# DAC.net
KiCad netlist of a schematic drawn in Altium Designer
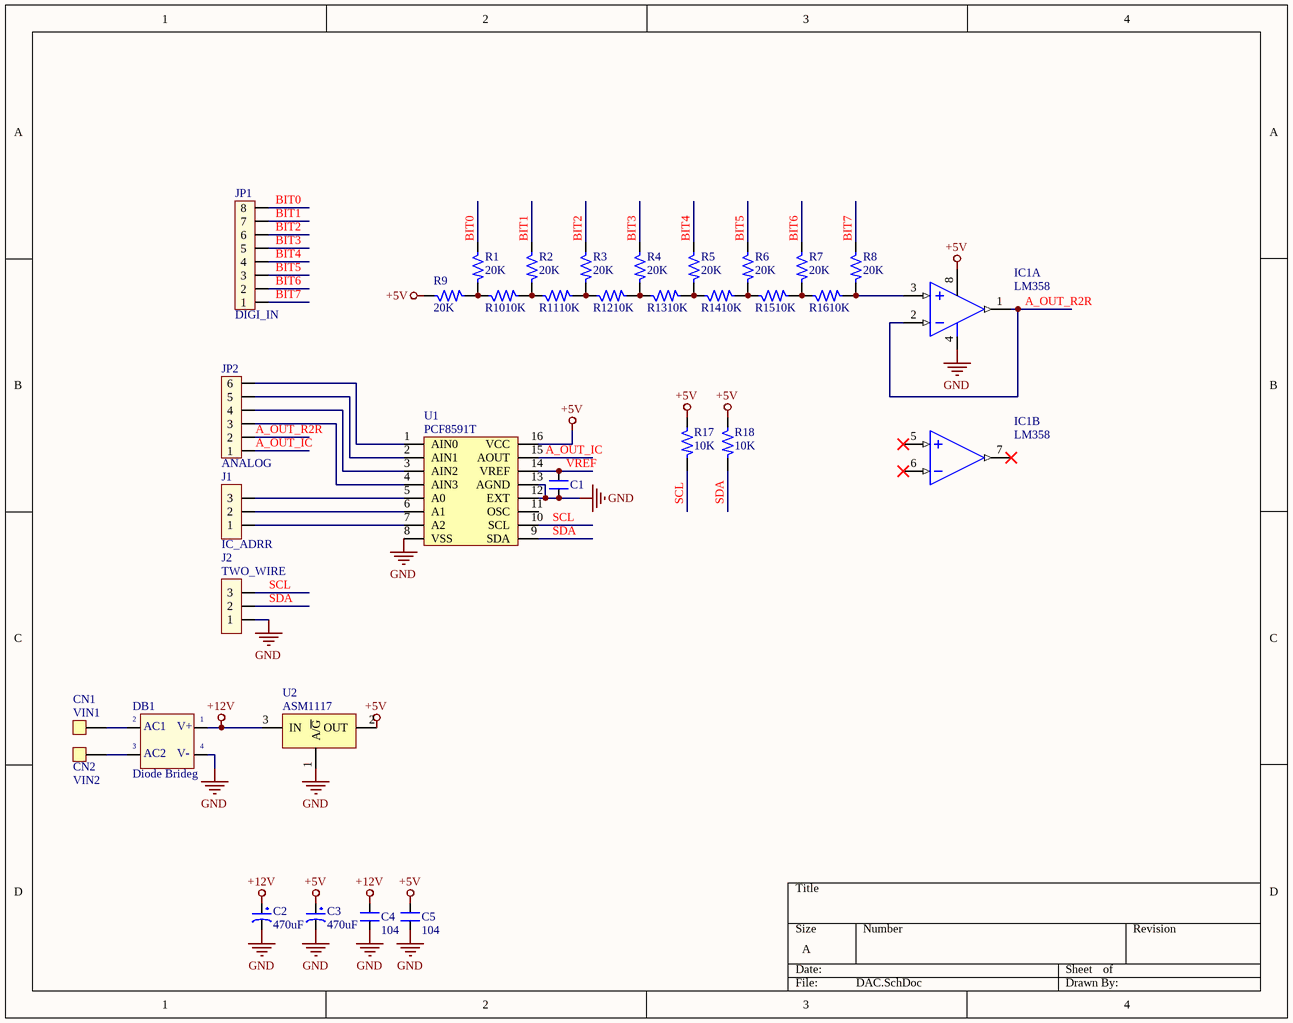
[diagram p0: DAC.SchDoc]

(export (version "E")
  (design (tool "Eeschema 10.0.6"))
  (components
    (comp (ref "C1")
      (value "104")
      (footprint "C-0805")
      (fields (field (name "DESIGNED BY") "VanDungEvn"))
      (libsource (lib "syhaunguyen") (part "CN"))
    )
    (comp (ref "C2")
      (value "470uF")
      (footprint "C-ALU-D6.5")
      (description "Cap P  0,1uF < 22uF , 16 - 50V")
      (libsource (lib "PART") (part "CP1"))
    )
    (comp (ref "C3")
      (value "470uF")
      (footprint "C-ALU-D6.5")
      (description "Cap P  0,1uF < 22uF , 16 - 50V")
      (libsource (lib "PART") (part "CP1"))
    )
    (comp (ref "C4")
      (value "104")
      (footprint "C-0805")
      (fields (field (name "DESIGNED BY") "VanDungEvn"))
      (libsource (lib "syhaunguyen") (part "CN"))
    )
    (comp (ref "C5")
      (value "104")
      (footprint "C-0805")
      (fields (field (name "DESIGNED BY") "VanDungEvn"))
      (libsource (lib "syhaunguyen") (part "CN"))
    )
    (comp (ref "CN1")
      (value "VIN1")
      (footprint "M3")
      (libsource (lib "doAnTotNghiep2017Lib") (part "COCDONGM3"))
    )
    (comp (ref "CN2")
      (value "VIN2")
      (footprint "M3")
      (libsource (lib "doAnTotNghiep2017Lib") (part "COCDONGM3"))
    )
    (comp (ref "DB1")
      (value "Diode Brideg")
      (footprint "D-DB-1A-SMD")
      (description "Convert AC to DC voltage, 4 pin")
      (libsource (lib "PART") (part "DB"))
    )
    (comp (ref "IC1")
      (value "LM358")
      (footprint "SOP-8")
      (description "Low-Power Dual Operational Amplifier")
      (libsource (lib "syhaunguyen") (part "LM358"))
    )
    (comp (ref "J1")
      (value "IC_ADRR")
      (footprint "JP3")
      (description "Jumper 3")
      (libsource (lib "syhaunguyen") (part "JP3"))
    )
    (comp (ref "J2")
      (value "TWO_WIRE")
      (footprint "JP3")
      (description "Jumper 3")
      (libsource (lib "syhaunguyen") (part "JP3"))
    )
    (comp (ref "JP1")
      (value "DIGI_IN")
      (footprint "JP8")
      (description "JP8 PIN")
      (libsource (lib "syhaunguyen") (part "JP8"))
    )
    (comp (ref "JP2")
      (value "ANALOG")
      (footprint "JP6")
      (description "JP6 PIN")
      (libsource (lib "syhaunguyen") (part "JP6"))
    )
    (comp (ref "R1")
      (value "20K")
      (footprint "R-0805")
      (description "Resistor 1/4W")
      (libsource (lib "syhaunguyen") (part "R"))
    )
    (comp (ref "R2")
      (value "20K")
      (footprint "R-0805")
      (description "Resistor 1/4W")
      (libsource (lib "syhaunguyen") (part "R"))
    )
    (comp (ref "R3")
      (value "20K")
      (footprint "R-0805")
      (description "Resistor 1/4W")
      (libsource (lib "syhaunguyen") (part "R"))
    )
    (comp (ref "R4")
      (value "20K")
      (footprint "R-0805")
      (description "Resistor 1/4W")
      (libsource (lib "syhaunguyen") (part "R"))
    )
    (comp (ref "R5")
      (value "20K")
      (footprint "R-0805")
      (description "Resistor 1/4W")
      (libsource (lib "syhaunguyen") (part "R"))
    )
    (comp (ref "R6")
      (value "20K")
      (footprint "R-0805")
      (description "Resistor 1/4W")
      (libsource (lib "syhaunguyen") (part "R"))
    )
    (comp (ref "R7")
      (value "20K")
      (footprint "R-0805")
      (description "Resistor 1/4W")
      (libsource (lib "syhaunguyen") (part "R"))
    )
    (comp (ref "R8")
      (value "20K")
      (footprint "R-0805")
      (description "Resistor 1/4W")
      (libsource (lib "syhaunguyen") (part "R"))
    )
    (comp (ref "R9")
      (value "20K")
      (footprint "R-0805")
      (description "Resistor 1/4W")
      (libsource (lib "syhaunguyen") (part "R"))
    )
    (comp (ref "R10")
      (value "10K")
      (footprint "R-0805")
      (description "Resistor 1/4W")
      (libsource (lib "syhaunguyen") (part "R"))
    )
    (comp (ref "R11")
      (value "10K")
      (footprint "R-0805")
      (description "Resistor 1/4W")
      (libsource (lib "syhaunguyen") (part "R"))
    )
    (comp (ref "R12")
      (value "10K")
      (footprint "R-0805")
      (description "Resistor 1/4W")
      (libsource (lib "syhaunguyen") (part "R"))
    )
    (comp (ref "R13")
      (value "10K")
      (footprint "R-0805")
      (description "Resistor 1/4W")
      (libsource (lib "syhaunguyen") (part "R"))
    )
    (comp (ref "R14")
      (value "10K")
      (footprint "R-0805")
      (description "Resistor 1/4W")
      (libsource (lib "syhaunguyen") (part "R"))
    )
    (comp (ref "R15")
      (value "10K")
      (footprint "R-0805")
      (description "Resistor 1/4W")
      (libsource (lib "syhaunguyen") (part "R"))
    )
    (comp (ref "R16")
      (value "10K")
      (footprint "R-0805")
      (description "Resistor 1/4W")
      (libsource (lib "syhaunguyen") (part "R"))
    )
    (comp (ref "R17")
      (value "10K")
      (footprint "R-0805")
      (description "Resistor 1/4W")
      (libsource (lib "syhaunguyen") (part "R"))
    )
    (comp (ref "R18")
      (value "10K")
      (footprint "R-0805")
      (description "Resistor 1/4W")
      (libsource (lib "syhaunguyen") (part "R"))
    )
    (comp (ref "U1")
      (value "PCF8591T")
      (footprint "SO-16")
      (libsource (lib "doAnTotNghiep2017Lib") (part "PCF8591T"))
    )
    (comp (ref "U2")
      (value "ASM1117")
      (footprint "TO-252")
      (libsource (lib "doAnTotNghiep2017Lib") (part "ASM1117"))
    )
  )
  (nets
    (net (code "1") (name "+5V") (class "Default")
      (node (ref "C3") (pin "1") (pinfunction "1_1") (pintype "passive"))
      (node (ref "C5") (pin "2") (pinfunction "2_2") (pintype "passive"))
      (node (ref "IC1") (pin "8") (pinfunction "+V_8") (pintype "passive"))
      (node (ref "R17") (pin "1") (pinfunction "1_1") (pintype "passive"))
      (node (ref "R18") (pin "1") (pinfunction "1_1") (pintype "passive"))
      (node (ref "R9") (pin "1") (pinfunction "1_1") (pintype "passive"))
      (node (ref "U1") (pin "16") (pinfunction "VCC_16") (pintype "passive"))
      (node (ref "U2") (pin "2") (pinfunction "OUT_2") (pintype "passive"))
    )
    (net (code "2") (name "+12V") (class "Default")
      (node (ref "C2") (pin "1") (pinfunction "1_1") (pintype "passive"))
      (node (ref "C4") (pin "2") (pinfunction "2_2") (pintype "passive"))
      (node (ref "DB1") (pin "3") (pinfunction "AC2_3") (pintype "passive"))
      (node (ref "U2") (pin "3") (pinfunction "IN_3") (pintype "passive"))
    )
    (net (code "3") (name "/A_OUT_IC") (class "Default")
      (node (ref "JP2") (pin "1") (pinfunction "1_1") (pintype "passive"))
      (node (ref "U1") (pin "15") (pinfunction "AOUT_15") (pintype "passive"))
    )
    (net (code "4") (name "/A_OUT_R2R") (class "Default")
      (node (ref "IC1") (pin "1") (pinfunction "OUT_1") (pintype "output"))
      (node (ref "IC1") (pin "2") (pinfunction "IN-_2") (pintype "input"))
      (node (ref "JP2") (pin "2") (pinfunction "2_2") (pintype "passive"))
    )
    (net (code "5") (name "/BIT0") (class "Default")
      (node (ref "JP1") (pin "8") (pinfunction "8_8") (pintype "passive"))
      (node (ref "R1") (pin "1") (pinfunction "1_1") (pintype "passive"))
    )
    (net (code "6") (name "/BIT1") (class "Default")
      (node (ref "JP1") (pin "7") (pinfunction "7_7") (pintype "passive"))
      (node (ref "R2") (pin "1") (pinfunction "1_1") (pintype "passive"))
    )
    (net (code "7") (name "/BIT2") (class "Default")
      (node (ref "JP1") (pin "6") (pinfunction "6_6") (pintype "passive"))
      (node (ref "R3") (pin "1") (pinfunction "1_1") (pintype "passive"))
    )
    (net (code "8") (name "/BIT3") (class "Default")
      (node (ref "JP1") (pin "5") (pinfunction "5_5") (pintype "passive"))
      (node (ref "R4") (pin "1") (pinfunction "1_1") (pintype "passive"))
    )
    (net (code "9") (name "/BIT4") (class "Default")
      (node (ref "JP1") (pin "4") (pinfunction "4_4") (pintype "passive"))
      (node (ref "R5") (pin "1") (pinfunction "1_1") (pintype "passive"))
    )
    (net (code "10") (name "/BIT5") (class "Default")
      (node (ref "JP1") (pin "3") (pinfunction "3_3") (pintype "passive"))
      (node (ref "R6") (pin "1") (pinfunction "1_1") (pintype "passive"))
    )
    (net (code "11") (name "/BIT6") (class "Default")
      (node (ref "JP1") (pin "2") (pinfunction "2_2") (pintype "passive"))
      (node (ref "R7") (pin "1") (pinfunction "1_1") (pintype "passive"))
    )
    (net (code "12") (name "/BIT7") (class "Default")
      (node (ref "JP1") (pin "1") (pinfunction "1_1") (pintype "passive"))
      (node (ref "R8") (pin "1") (pinfunction "1_1") (pintype "passive"))
    )
    (net (code "13") (name "/SCL") (class "Default")
      (node (ref "J2") (pin "3") (pinfunction "3_3") (pintype "passive"))
      (node (ref "R17") (pin "2") (pinfunction "2_2") (pintype "passive"))
      (node (ref "U1") (pin "10") (pinfunction "SCL_10") (pintype "passive"))
    )
    (net (code "14") (name "/SDA") (class "Default")
      (node (ref "J2") (pin "2") (pinfunction "2_2") (pintype "passive"))
      (node (ref "R18") (pin "2") (pinfunction "2_2") (pintype "passive"))
      (node (ref "U1") (pin "9") (pinfunction "SDA_9") (pintype "passive"))
    )
    (net (code "15") (name "/VREF") (class "Default")
      (node (ref "C1") (pin "2") (pinfunction "2_2") (pintype "passive"))
      (node (ref "U1") (pin "14") (pinfunction "VREF_14") (pintype "passive"))
    )
    (net (code "16") (name "GND") (class "Default")
      (node (ref "C1") (pin "1") (pinfunction "1_1") (pintype "passive"))
      (node (ref "C2") (pin "2") (pinfunction "2_2") (pintype "passive"))
      (node (ref "C3") (pin "2") (pinfunction "2_2") (pintype "passive"))
      (node (ref "C4") (pin "1") (pinfunction "1_1") (pintype "passive"))
      (node (ref "C5") (pin "1") (pinfunction "1_1") (pintype "passive"))
      (node (ref "DB1") (pin "4") (pinfunction "-V_OUT_4") (pintype "passive"))
      (node (ref "IC1") (pin "4") (pinfunction "-V_4") (pintype "passive"))
      (node (ref "J2") (pin "1") (pinfunction "1_1") (pintype "passive"))
      (node (ref "U1") (pin "12") (pinfunction "EXT_12") (pintype "passive"))
      (node (ref "U1") (pin "13") (pinfunction "AGND_13") (pintype "passive"))
      (node (ref "U1") (pin "8") (pinfunction "VSS_8") (pintype "passive"))
      (node (ref "U2") (pin "1") (pinfunction "A/~{G}_1") (pintype "passive"))
    )
    (net (code "17") (name "Net-(DB1-+V_OUT)") (class "Default")
      (node (ref "CN2") (pin "1") (pintype "passive"))
      (node (ref "DB1") (pin "1") (pinfunction "+V_OUT_1") (pintype "passive"))
    )
    (net (code "18") (name "Net-(DB1-AC1)") (class "Default")
      (node (ref "CN1") (pin "1") (pintype "passive"))
      (node (ref "DB1") (pin "2") (pinfunction "AC1_2") (pintype "passive"))
    )
    (net (code "19") (name "Net-(IC1A-IN+)") (class "Default")
      (node (ref "IC1") (pin "3") (pinfunction "IN+_3") (pintype "input"))
      (node (ref "R16") (pin "2") (pinfunction "2_2") (pintype "passive"))
      (node (ref "R8") (pin "2") (pinfunction "2_2") (pintype "passive"))
    )
    (net (code "20") (name "Net-(R1-Pad2)") (class "Default")
      (node (ref "R1") (pin "2") (pinfunction "2_2") (pintype "passive"))
      (node (ref "R10") (pin "1") (pinfunction "1_1") (pintype "passive"))
      (node (ref "R9") (pin "2") (pinfunction "2_2") (pintype "passive"))
    )
    (net (code "21") (name "Net-(R10-Pad2)") (class "Default")
      (node (ref "R10") (pin "2") (pinfunction "2_2") (pintype "passive"))
      (node (ref "R11") (pin "1") (pinfunction "1_1") (pintype "passive"))
      (node (ref "R2") (pin "2") (pinfunction "2_2") (pintype "passive"))
    )
    (net (code "22") (name "Net-(R11-Pad2)") (class "Default")
      (node (ref "R11") (pin "2") (pinfunction "2_2") (pintype "passive"))
      (node (ref "R12") (pin "1") (pinfunction "1_1") (pintype "passive"))
      (node (ref "R3") (pin "2") (pinfunction "2_2") (pintype "passive"))
    )
    (net (code "23") (name "Net-(R12-Pad2)") (class "Default")
      (node (ref "R12") (pin "2") (pinfunction "2_2") (pintype "passive"))
      (node (ref "R13") (pin "1") (pinfunction "1_1") (pintype "passive"))
      (node (ref "R4") (pin "2") (pinfunction "2_2") (pintype "passive"))
    )
    (net (code "24") (name "Net-(R13-Pad2)") (class "Default")
      (node (ref "R13") (pin "2") (pinfunction "2_2") (pintype "passive"))
      (node (ref "R14") (pin "1") (pinfunction "1_1") (pintype "passive"))
      (node (ref "R5") (pin "2") (pinfunction "2_2") (pintype "passive"))
    )
    (net (code "25") (name "Net-(R14-Pad2)") (class "Default")
      (node (ref "R14") (pin "2") (pinfunction "2_2") (pintype "passive"))
      (node (ref "R15") (pin "1") (pinfunction "1_1") (pintype "passive"))
      (node (ref "R6") (pin "2") (pinfunction "2_2") (pintype "passive"))
    )
    (net (code "26") (name "Net-(R15-Pad2)") (class "Default")
      (node (ref "R15") (pin "2") (pinfunction "2_2") (pintype "passive"))
      (node (ref "R16") (pin "1") (pinfunction "1_1") (pintype "passive"))
      (node (ref "R7") (pin "2") (pinfunction "2_2") (pintype "passive"))
    )
    (net (code "27") (name "Net-(U1-A0)") (class "Default")
      (node (ref "J1") (pin "3") (pinfunction "3_3") (pintype "passive"))
      (node (ref "U1") (pin "5") (pinfunction "A0_5") (pintype "passive"))
    )
    (net (code "28") (name "Net-(U1-A1)") (class "Default")
      (node (ref "J1") (pin "2") (pinfunction "2_2") (pintype "passive"))
      (node (ref "U1") (pin "6") (pinfunction "A1_6") (pintype "passive"))
    )
    (net (code "29") (name "Net-(U1-A2)") (class "Default")
      (node (ref "J1") (pin "1") (pinfunction "1_1") (pintype "passive"))
      (node (ref "U1") (pin "7") (pinfunction "A2_7") (pintype "passive"))
    )
    (net (code "30") (name "Net-(U1-AIN0)") (class "Default")
      (node (ref "JP2") (pin "6") (pinfunction "6_6") (pintype "passive"))
      (node (ref "U1") (pin "1") (pinfunction "AIN0_1") (pintype "passive"))
    )
    (net (code "31") (name "Net-(U1-AIN1)") (class "Default")
      (node (ref "JP2") (pin "5") (pinfunction "5_5") (pintype "passive"))
      (node (ref "U1") (pin "2") (pinfunction "AIN1_2") (pintype "passive"))
    )
    (net (code "32") (name "Net-(U1-AIN2)") (class "Default")
      (node (ref "JP2") (pin "4") (pinfunction "4_4") (pintype "passive"))
      (node (ref "U1") (pin "3") (pinfunction "AIN2_3") (pintype "passive"))
    )
    (net (code "33") (name "Net-(U1-AIN3)") (class "Default")
      (node (ref "JP2") (pin "3") (pinfunction "3_3") (pintype "passive"))
      (node (ref "U1") (pin "4") (pinfunction "AIN3_4") (pintype "passive"))
    )
    (net (code "34") (name "unconnected-(IC1B-IN+-Pad5)") (class "Default")
      (node (ref "IC1") (pin "5") (pinfunction "IN+_5") (pintype "input+no_connect"))
    )
    (net (code "35") (name "unconnected-(IC1B-IN--Pad6)") (class "Default")
      (node (ref "IC1") (pin "6") (pinfunction "IN-_6") (pintype "input+no_connect"))
    )
    (net (code "36") (name "unconnected-(IC1B-OUT-Pad7)") (class "Default")
      (node (ref "IC1") (pin "7") (pinfunction "OUT_7") (pintype "output+no_connect"))
    )
    (net (code "37") (name "unconnected-(U1-OSC-Pad11)") (class "Default")
      (node (ref "U1") (pin "11") (pinfunction "OSC_11") (pintype "passive"))
    )
  )
)
